# REG113-25_sch.net
KiCad netlist of a schematic drawn in Altium Designer
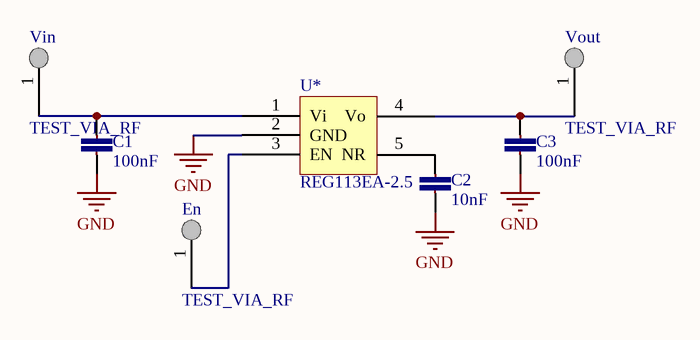
[diagram p0: REG113-25_sch.SchDoc]

(export (version "E")
  (design (tool "Eeschema 10.0.6"))
  (components
    (comp (ref "C1")
      (value "100nF")
      (footprint "0402-CAP")
      (description "CAP CER 0.1UF 50V 10% X7R 0402")
      (fields (field (name "PART NO") "C1005X7R1H104K050BB"))
      (libsource (lib "IMBEL") (part "CAPACITOR"))
    )
    (comp (ref "C2")
      (value "10nF")
      (footprint "0402-CAP")
      (description "CAP CER 10000PF 25V 5% X7R 0402")
      (fields (field (name "PART NO") "GRM155R71E103JA01J"))
      (libsource (lib "IMBEL") (part "CAPACITOR"))
    )
    (comp (ref "C3")
      (value "100nF")
      (footprint "0402-CAP")
      (description "CAP CER 0.1UF 50V 10% X7R 0402")
      (fields (field (name "PART NO") "C1005X7R1H104K050BB"))
      (libsource (lib "IMBEL") (part "CAPACITOR"))
    )
    (comp (ref "En")
      (value "TEST_VIA_RF")
      (footprint "New footprint 1")
      (description "Test VIA for RF circuits")
      (libsource (lib "IMBEL") (part "TEST_VIA"))
    )
    (comp (ref "U*")
      (value "REG113EA-2.5")
      (footprint "SOT95P280X145-5N")
      (description "IC REG LINEAR 2.5V 400MA 8VSSOP")
      (libsource (lib "IMBEL") (part "REG113"))
    )
    (comp (ref "Vin")
      (value "TEST_VIA_RF")
      (footprint "New footprint 1")
      (description "Test VIA for RF circuits")
      (libsource (lib "IMBEL") (part "TEST_VIA"))
    )
    (comp (ref "Vout")
      (value "TEST_VIA_RF")
      (footprint "New footprint 1")
      (description "Test VIA for RF circuits")
      (libsource (lib "IMBEL") (part "TEST_VIA"))
    )
  )
  (nets
    (net (code "1") (name "GND") (class "Default")
      (node (ref "C1") (pin "2") (pinfunction "2_2") (pintype "passive"))
      (node (ref "C2") (pin "2") (pinfunction "2_2") (pintype "passive"))
      (node (ref "C3") (pin "2") (pinfunction "2_2") (pintype "passive"))
      (node (ref "U*") (pin "2") (pinfunction "GND_2") (pintype "passive"))
    )
    (net (code "2") (name "Net-(U*-EN)") (class "Default")
      (node (ref "En") (pin "1") (pinfunction "1_1") (pintype "passive"))
      (node (ref "U*") (pin "3") (pinfunction "EN_3") (pintype "passive"))
    )
    (net (code "3") (name "Net-(U*-NR)") (class "Default")
      (node (ref "C2") (pin "1") (pinfunction "1_1") (pintype "passive"))
      (node (ref "U*") (pin "5") (pinfunction "NR_5") (pintype "passive"))
    )
    (net (code "4") (name "Net-(U*-Vi)") (class "Default")
      (node (ref "C1") (pin "1") (pinfunction "1_1") (pintype "passive"))
      (node (ref "U*") (pin "1") (pinfunction "Vi_1") (pintype "passive"))
      (node (ref "Vin") (pin "1") (pinfunction "1_1") (pintype "passive"))
    )
    (net (code "5") (name "Net-(U*-Vo)") (class "Default")
      (node (ref "C3") (pin "1") (pinfunction "1_1") (pintype "passive"))
      (node (ref "U*") (pin "4") (pinfunction "Vo_4") (pintype "passive"))
      (node (ref "Vout") (pin "1") (pinfunction "1_1") (pintype "passive"))
    )
  )
)
